# Energy-Meter.net
KiCad netlist of a schematic drawn in Altium Designer
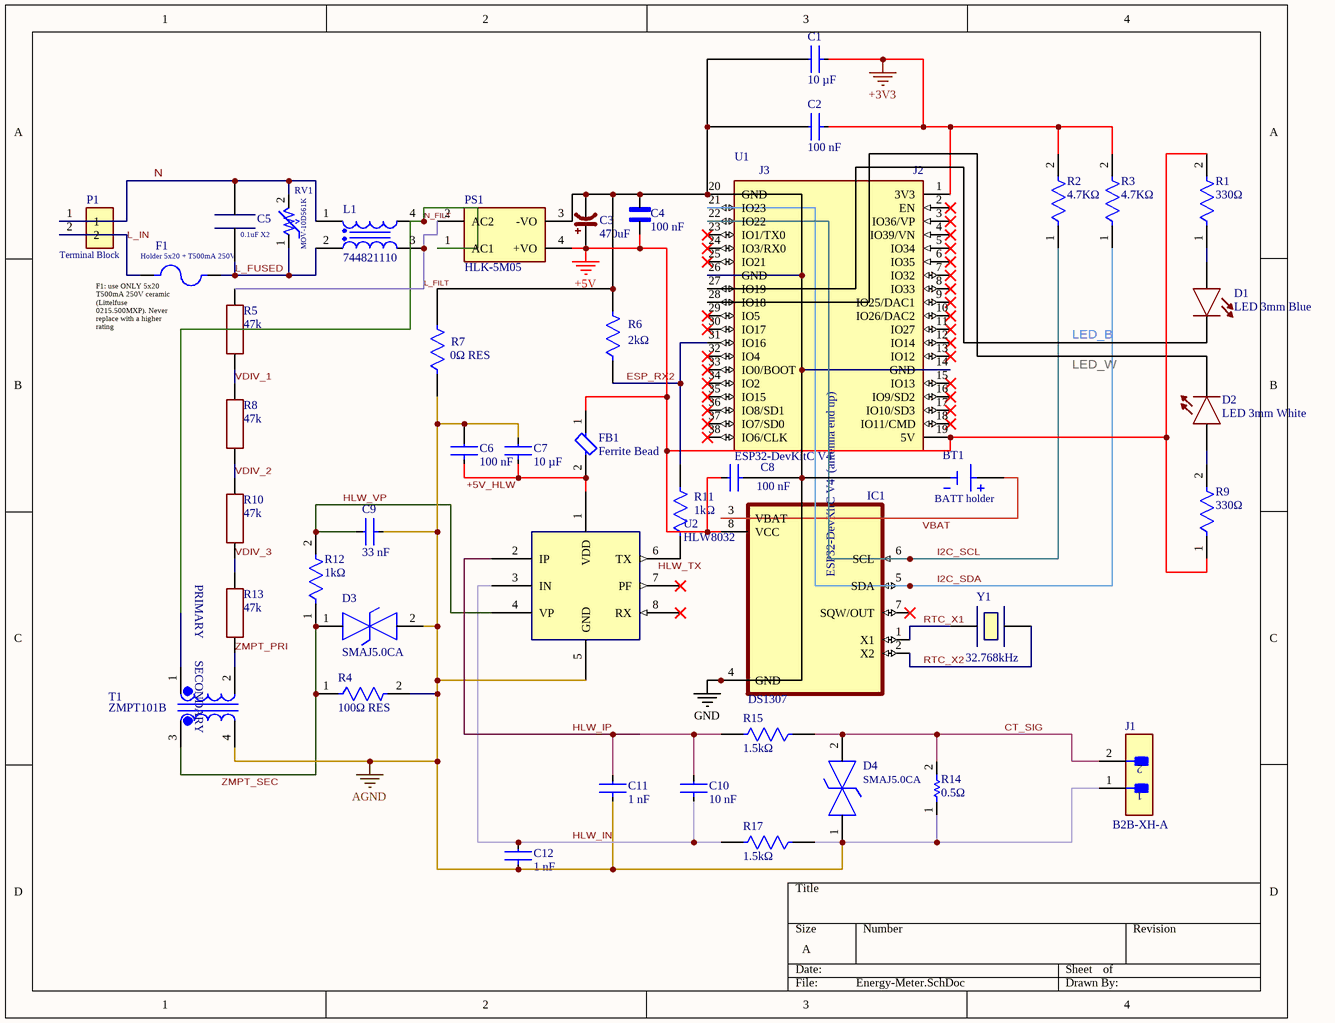
[diagram p0: Energy-Meter.SchDoc]

(export (version "E")
  (design (tool "Eeschema 10.0.6"))
  (components
    (comp (ref "BT1")
      (value "BATT holder")
      (footprint "BAT_BH32T-C-G")
      (description "BATTERY HOLDER COIN 20MM PC PIN")
      (fields (field (name "MANUFACTURER") "MPD") (field (name "MANUFACTURER PART NUMBER") "BH32T-C-G"))
      (libsource (lib "BH32T-C-G") (part "BH32T-C-G"))
    )
    (comp (ref "C1")
      (value "10 µF")
      (footprint "FP-1206-L_3_2_0_2-W_1_6_0-MFG")
      (description "General Purpose Ceramic Capacitor, 1206, 10uF, 10%, X5R, 15%, 10V")
      (fields (field (name "TOLERANCE") "10%") (field (name "VOLTAGE") "10V"))
      (libsource (lib "Components - 24.09.26 - 14.46") (part "CMP-04427-021870-1"))
    )
    (comp (ref "C2")
      (value "100 nF")
      (footprint "FP-C1206C-EB-MFG")
      (description "CAP CER 0.1UF 25V X7R 1206")
      (fields
        (field (name "OCTOPART") "https://octopart.com/c1206c104j3ractu-kemet-9140182")
        (field (name "MANUFACTURER") "KEMET")
      )
      (libsource (lib "Components - 24.09.26 - 14.39") (part "CMP-03020-014296-1"))
    )
    (comp (ref "C3")
      (value "470uF")
      (footprint "CAPPRD350W60D800H1150_LAYDOWN")
      (description "Capacitor, aluminium electrolytic, 470 uF, 10 V, 20%, radial D8x11.5mm, 3.5mm pitch, laid down")
      (fields (field (name "TOLERANCE") "±20%") (field (name "MANUFACTURER") "Rubycon"))
      (libsource (lib "Capacitor_470uF_10V_LayDown") (part "CAP_POL_470UF_10V_D8X11.5_LD"))
    )
    (comp (ref "C4")
      (value "100 nF")
      (footprint "CAPRR508W50L508T318H762")
      (description "AR 100nF Ceramic Multilayer Cap,50V dc,+125C,X7R Dielectric,+/-10%,Through Hole ¦ AVX AR215C104K4R")
      (fields (field (name "MANUFACTURER") "AVX") (field (name "MANUFACTURER PART NUMBER") "AR215C104K4R"))
      (libsource (lib "AR215C104K4R") (part "AR215C104K4R"))
    )
    (comp (ref "C5")
      (value "0.1uF X2")
      (footprint "CAPX2_L18.0-W6.0-H11.0_P15.00")
      (fields
        (field (name "MANUFACTURER") "TDK")
        (field (name "MANUFACTURER PART NUMBER") "B32922C3104K000")
        (field (name "TOLERANCE") "+/-10% (K)")
      )
      (libsource (lib "0.1uf-x2-capacitor") (part "CAP-X2-0.1uF-275VAC"))
    )
    (comp (ref "C6")
      (value "100 nF")
      (footprint "FP-C1206C-EB-MFG")
      (description "CAP CER 0.1UF 25V X7R 1206")
      (fields
        (field (name "OCTOPART") "https://octopart.com/c1206c104j3ractu-kemet-9140182")
        (field (name "MANUFACTURER") "KEMET")
      )
      (libsource (lib "Components - 24.09.26 - 14.39") (part "CMP-03020-014296-1"))
    )
    (comp (ref "C7")
      (value "10 µF")
      (footprint "FP-GRM31C-0_2-e0_3_0_8-IPC_C")
      (description "Chip Multilayer Ceramic Capacitors for General Purpose, 1206, 10uF, X7R, 15%, 10%, 25V")
      (fields (field (name "TOLERANCE") "10%") (field (name "VOLTAGE") "25V"))
      (libsource (lib "Components - 04.10.26 - 11.53") (part "CMP-06035-005515-1"))
    )
    (comp (ref "C8")
      (value "100 nF")
      (footprint "FP-C1206C-EB-MFG")
      (description "CAP CER 0.1UF 25V X7R 1206")
      (fields
        (field (name "OCTOPART") "https://octopart.com/c1206c104j3ractu-kemet-9140182")
        (field (name "MANUFACTURER") "KEMET")
      )
      (libsource (lib "Components - 24.09.26 - 14.39") (part "CMP-03020-014296-1"))
    )
    (comp (ref "C9")
      (value "33 nF")
      (footprint "FP-C1206C-EB-MFG")
      (description "C1206 33,000 pF C0G 5.00% 50 V")
      (fields
        (field (name "MANUFACTURER") "KEMET")
        (field (name "MANUFACTURER PART NUMBER") "C1206C333J5GACAUTO")
      )
      (libsource (lib "Components - 05.10.26 - 13.04") (part "CMP-03020-013243-1"))
    )
    (comp (ref "C10")
      (value "10 nF")
      (footprint "FP-C1206C-EB-MFG")
      (description "CAP CER 10000PF 100V C0G 1206")
      (fields
        (field (name "OCTOPART") "https://octopart.com/c1206c103j1gacauto-kemet-84841126")
        (field (name "TOLERANCE") "0.05")
      )
      (libsource (lib "Components - 05.10.26 - 11.35") (part "CMP-03020-012568-1"))
    )
    (comp (ref "C11")
      (value "1 nF")
      (footprint "FP-C1206C-EB-MFG")
      (description "C1206 1,000 pF C0G 5.00% 200 V")
      (fields
        (field (name "MANUFACTURER PART NUMBER") "C1206C102J2GACAUTO")
        (field (name "MANUFACTURER") "KEMET")
      )
      (libsource (lib "Components - 05.10.26 - 10.58") (part "CMP-03020-025981-1"))
    )
    (comp (ref "C12")
      (value "1 nF")
      (footprint "FP-C1206C-EB-MFG")
      (description "C1206 1,000 pF C0G 5.00% 200 V")
      (fields
        (field (name "MANUFACTURER PART NUMBER") "C1206C102J2GACAUTO")
        (field (name "MANUFACTURER") "KEMET")
      )
      (libsource (lib "Components - 05.10.26 - 10.58") (part "CMP-03020-025981-1"))
    )
    (comp (ref "D1")
      (value "LED 3mm Blue")
      (footprint "LED_D3.0MM_P2.54_BLUE")
      (description "LED, 3mm round, blue diffused, THT 2.54mm")
      (fields
        (field (name "MANUFACTURER") "Kingbright")
        (field (name "MANUFACTURER PART NUMBER") "WP710A10QBD/D")
      )
      (libsource (lib "LED_3mm_Blue_Diffused") (part "LED_3MM_BLUE_DIFFUSED"))
    )
    (comp (ref "D2")
      (value "LED 3mm White")
      (footprint "LED_D3.0MM_P2.54_WHITE")
      (description "LED, 3mm round, white diffused, THT 2.54mm")
      (fields
        (field (name "MANUFACTURER") "Kingbright")
        (field (name "MANUFACTURER PART NUMBER") "L-7104QWC-D")
      )
      (libsource (lib "LED_3mm_White_Diffused") (part "LED_3MM_WHITE_DIFFUSED"))
    )
    (comp (ref "D3")
      (value "SMAJ5.0CA")
      (footprint "FP-SMAJ-MFG")
      (description "TVS DIODE 5V 9.2V SMA")
      (fields
        (field (name "MANUFACTURER") "Bourns Inc.")
        (field (name "OCTOPART") "https://octopart.com/smaj5.0ca-bourns-12809390")
      )
      (libsource (lib "Components - 24.09.26 - 15.01") (part "CMP-2000-07091-2"))
    )
    (comp (ref "D4")
      (value "SMAJ5.0CA")
      (footprint "FP-SMAJ-MFG")
      (description "TVS DIODE 5V 9.2V SMA")
      (fields
        (field (name "MANUFACTURER") "Bourns Inc.")
        (field (name "OCTOPART") "https://octopart.com/smaj5.0ca-bourns-12809390")
      )
      (libsource (lib "Components - 24.09.26 - 15.01") (part "CMP-2000-07091-2"))
    )
    (comp (ref "F1")
      (value "Holder 5x20 + T500mA 250V")
      (footprint "FUSE_4628")
      (description "5mm Slim Line Fuse holder")
      (fields (field (name "MANUFACTURER") "Keystone") (field (name "MANUFACTURER PART NUMBER") "4628"))
      (libsource (lib "4628") (part "4628"))
    )
    (comp (ref "FB1")
      (value "Ferrite Bead")
      (footprint "FP-BLM31-0_2-t1_6-IPC_B")
      (description "Chip Ferrite Bead, 1206, 600Ω @ 100MHz, 0.038Ω, 25%, 2.9A")
      (fields (field (name "MANUFACTURER") "125°C"))
      (libsource (lib "Components - 20.09.26 - 18.12") (part "CMP-06046-002432-1"))
    )
    (comp (ref "IC1")
      (value "DS1307")
      (footprint "DIP794W47P254L991H457Q8")
      (description "Real Time Clock (RTC) I²C, 56 B RAM, 8-DIP")
      (fields
        (field (name "MANUFACTURER") "Analog Devices")
        (field (name "MANUFACTURER PART NUMBER") "DS1307+")
      )
      (libsource (lib "DS1307") (part "DS1307"))
    )
    (comp (ref "J1")
      (value "B2B-XH-A")
      (footprint "FP-B2B-XH-AM_LF_SN-MFG")
      (description "CONN HEADER VERT 2POS 2.5MM")
      (fields
        (field (name "MANUFACTURER") "JST")
        (field (name "MANUFACTURER PART NUMBER") "B2B-XH-AM(LF)(SN)")
      )
      (libsource (lib "Components - 27.09.26 - 13.44") (part "CMP-17439-000037-1"))
    )
    (comp (ref "L1")
      (value "744821110")
      (footprint "WE-CMB_Type XS_L15W7.5H18")
      (fields (field (name "TOLERANCE") "30%") (field (name "MANUFACTURER") "Wurth Elektronik"))
      (libsource (lib "Components - 02.10.26 - 18.05") (part "CMP-0223-00077-2"))
    )
    (comp (ref "P1")
      (value "Terminal Block")
      (footprint "TE_282837-2")
      (fields
        (field (name "MANUFACTURER") "TE Connectivity")
        (field (name "MANUFACTURER PART NUMBER") "282837-2")
      )
      (libsource (lib "282837-2") (part "282837-2"))
    )
    (comp (ref "PS1")
      (value "HLK-5M05")
      (footprint "CONV_HLK-5M05")
      (description "AC DC 220V to 5V 5W 5Watt Isolated Switching Step-Down Power Supply Module Converter")
      (fields (field (name "MANUFACTURER") "Hi-link"))
      (libsource (lib "Smart-Energy-Meter") (part "HLK-5M05"))
    )
    (comp (ref "R1")
      (value "330Ω")
      (footprint "FP-AC2512-MFG")
      (description "RES SMD 330 OHM 5% 1W 2512")
      (fields (field (name "MANUFACTURER") "Yageo") (field (name "TOLERANCE") "0.05"))
      (libsource (lib "Components - 27.09.26 - 08.47") (part "CMP-03412-030391-1"))
    )
    (comp (ref "R2")
      (value "4.7KΩ")
      (footprint "FP-AC2512-MFG")
      (description "RES SMD 4.7K OHM 1% 1W 2512")
      (fields
        (field (name "MANUFACTURER") "Yageo")
        (field (name "OCTOPART") "https://octopart.com/ac2512fk-074k7l-yageo-71370127")
      )
      (libsource (lib "Components - 26.09.26 - 14.01") (part "CMP-03412-032212-1"))
    )
    (comp (ref "R3")
      (value "4.7KΩ")
      (footprint "FP-AC2512-MFG")
      (description "RES SMD 4.7K OHM 1% 1W 2512")
      (fields
        (field (name "MANUFACTURER") "Yageo")
        (field (name "OCTOPART") "https://octopart.com/ac2512fk-074k7l-yageo-71370127")
      )
      (libsource (lib "Components - 26.09.26 - 14.01") (part "CMP-03412-032212-1"))
    )
    (comp (ref "R4")
      (value "100Ω RES")
      (footprint "FP-MCA1206-IPC_A")
      (description "Res MC AT Precision Thin Film 1206 100Ω 0.1% 0.4W ±25ppm/°C Molded Paper T/R")
      (fields (field (name "TOLERANCE") "0.1%") (field (name "MANUFACTURER") "Vishay"))
      (libsource (lib "Components - 04.10.26 - 07.59") (part "CMP-02407-001396-1"))
    )
    (comp (ref "R5")
      (value "47k")
      (footprint "RESAD762W55L630D240_MF")
      (description "Resistor, 47 kOhm, 1%, 0.25 W, metal film, axial THT, 7.62 mm pitch")
      (fields (field (name "TOLERANCE") "±1%") (field (name "POWER") "0.25W (1/4W)"))
      (libsource (lib "Resistor_47K_1pct_MetalFilm_THT") (part "RES_47K_0.25W_1PCT_MF_7.62MM"))
    )
    (comp (ref "R6")
      (value "2kΩ")
      (footprint "FP-CRCW2512-e3-IPC_A")
      (description "RES Thick Film, 2kΩ, 1%, 1W, 100ppm/°C, 2512")
      (fields (field (name "TOLERANCE") "1%") (field (name "MANUFACTURER") "Vishay"))
      (libsource (lib "Components - 27.09.26 - 07.57") (part "CMP-02407-009223-1"))
    )
    (comp (ref "R7")
      (value "0Ω RES")
      (footprint "FP-RMCF2512-IPC_A")
      (description "0Ω ±0 1W 2512 Thick Film Chip Resistor AEC-Q200 compliant")
      (fields (field (name "TOLERANCE") "5%") (field (name "MANUFACTURER") "Stackpole"))
      (libsource (lib "Components - 27.09.26 - 08.03") (part "CMP-26527-000191-1"))
    )
    (comp (ref "R8")
      (value "47k")
      (footprint "RESAD762W55L630D240_MF")
      (description "Resistor, 47 kOhm, 1%, 0.25 W, metal film, axial THT, 7.62 mm pitch")
      (fields (field (name "TOLERANCE") "±1%") (field (name "POWER") "0.25W (1/4W)"))
      (libsource (lib "Resistor_47K_1pct_MetalFilm_THT") (part "RES_47K_0.25W_1PCT_MF_7.62MM"))
    )
    (comp (ref "R9")
      (value "330Ω")
      (footprint "FP-AC2512-MFG")
      (description "RES SMD 330 OHM 5% 1W 2512")
      (fields (field (name "MANUFACTURER") "Yageo") (field (name "TOLERANCE") "0.05"))
      (libsource (lib "Components - 27.09.26 - 08.47") (part "CMP-03412-030391-1"))
    )
    (comp (ref "R10")
      (value "47k")
      (footprint "RESAD762W55L630D240_MF")
      (description "Resistor, 47 kOhm, 1%, 0.25 W, metal film, axial THT, 7.62 mm pitch")
      (fields (field (name "TOLERANCE") "±1%") (field (name "POWER") "0.25W (1/4W)"))
      (libsource (lib "Resistor_47K_1pct_MetalFilm_THT") (part "RES_47K_0.25W_1PCT_MF_7.62MM"))
    )
    (comp (ref "R11")
      (value "1kΩ")
      (footprint "FP-CRCW2512-e3-IPC_A")
      (description "RES Thick Film, 1kΩ, 1%, 1W, 100ppm/°C, 2512")
      (fields (field (name "TOLERANCE") "1%") (field (name "MANUFACTURER") "Vishay"))
      (libsource (lib "Components - 26.09.26 - 13.02") (part "CMP-02407-005908-1"))
    )
    (comp (ref "R12")
      (value "1kΩ")
      (footprint "FP-RMCF1206-IPC_C")
      (description "1kΩ ±1% 0.25W 1206 Thick Film Chip Resistor AEC-Q200 compliant")
      (fields (field (name "TOLERANCE") "1%") (field (name "MANUFACTURER") "155°C"))
      (libsource (lib "Components - 24.09.26 - 14.09") (part "CMP-26527-005571-1"))
    )
    (comp (ref "R13")
      (value "47k")
      (footprint "RESAD762W55L630D240_MF")
      (description "Resistor, 47 kOhm, 1%, 0.25 W, metal film, axial THT, 7.62 mm pitch")
      (fields (field (name "TOLERANCE") "±1%") (field (name "POWER") "0.25W (1/4W)"))
      (libsource (lib "Resistor_47K_1pct_MetalFilm_THT") (part "RES_47K_0.25W_1PCT_MF_7.62MM"))
    )
    (comp (ref "R14")
      (value "0.5Ω")
      (footprint "RESC6432X89X76ML25T25")
      (description "Chip Resistor, 0.5 Ohm, +/- 1%, 1 W, -65 to 275 degC, 2512 (6432 Metric), RoHS, Tape and Reel")
      (fields (field (name "TOLERANCE") "1%") (field (name "MANUFACTURER PART NUMBER") "WSLT2512R5000FEA"))
      (libsource (lib "Components - 04.10.26 - 11.37") (part "CMP-1666-00017-2"))
    )
    (comp (ref "R15")
      (value "1.5kΩ")
      (footprint "FP-CRCW2512-e3-IPC_A")
      (description "RES Thick Film, 1.5kΩ, 1%, 1W, 100ppm/°C, 2512")
      (fields (field (name "TOLERANCE") "1%") (field (name "MANUFACTURER") "Vishay"))
      (libsource (lib "Components - 26.09.26 - 13.06") (part "CMP-02407-008685-1"))
    )
    (comp (ref "R17")
      (value "1.5kΩ")
      (footprint "FP-CRCW2512-e3-IPC_A")
      (description "RES Thick Film, 1.5kΩ, 1%, 1W, 100ppm/°C, 2512")
      (fields (field (name "TOLERANCE") "1%") (field (name "MANUFACTURER") "Vishay"))
      (libsource (lib "Components - 26.09.26 - 13.06") (part "CMP-02407-008685-1"))
    )
    (comp (ref "RV1")
      (value "MOV-10D561K")
      (footprint "VAR_MOV-10D561K")
      (description "560 V 2.5 kA Varistor 1 Circuit Through Hole Disc 10mm")
      (fields (field (name "MANUFACTURER") "Bourns"))
      (libsource (lib "MOV-10D561K") (part "MOV-10D561K"))
    )
    (comp (ref "T1")
      (value "ZMPT101B")
      (footprint "XFMR_ZMPT101B")
      (description "Current-type Voltage Transformer")
      (fields (field (name "MANUFACTURER") "Qingxian Zeming Langxi Electronic"))
      (libsource (lib "ZMPT101B") (part "ZMPT101B"))
    )
    (comp (ref "U1")
      (value "ESP32-DevKitC V4")
      (footprint "ESP32-DEVKITC-V4_SOCKET")
      (description "Espressif ESP32-DevKitC V4 (ESP32-WROOM-32E) dev board, socketed on 2x19 female headers")
      (fields
        (field (name "MANUFACTURER") "Espressif Systems")
        (field (name "MANUFACTURER PART NUMBER") "ESP32-DEVKITC-32E")
      )
      (libsource (lib "ESP32_DevKitC_V4_Socket") (part "ESP32-DEVKITC-V4"))
    )
    (comp (ref "U2")
      (value "HLW8032")
      (footprint "SOIC127P600X175-8N")
      (fields (field (name "MANUFACTURER") "Hiliwei Tech"))
      (libsource (lib "Smart-Energy-Meter") (part "HLW8032"))
    )
    (comp (ref "Y1")
      (value "32.768kHz")
      (footprint "XTAL_D3.2xL8.3_P2.00_Vertical")
      (fields
        (field (name "TOLERANCE") "+/-20ppm")
        (field (name "MANUFACTURER PART NUMBER") "AB38T-32.768KHZ")
        (field (name "MANUFACTURER") "Abracon")
      )
      (libsource (lib "Crystal_32768") (part "XTAL-32.768kHz"))
    )
  )
  (nets
    (net (code "1") (name "+3V3") (class "Default")
      (node (ref "C1") (pin "1") (pinfunction "1_1") (pintype "passive"))
      (node (ref "C2") (pin "1") (pinfunction "1_1") (pintype "passive"))
      (node (ref "R2") (pin "2") (pinfunction "2_2") (pintype "passive"))
      (node (ref "R3") (pin "2") (pinfunction "2_2") (pintype "passive"))
      (node (ref "U1") (pin "1") (pinfunction "3V3_1") (pintype "power_in"))
    )
    (net (code "2") (name "+5V") (class "Default")
      (node (ref "C3") (pin "1") (pinfunction "+_1") (pintype "passive"))
      (node (ref "C4") (pin "1") (pinfunction "1_1") (pintype "passive"))
      (node (ref "C8") (pin "2") (pinfunction "2_2") (pintype "passive"))
      (node (ref "FB1") (pin "1") (pinfunction "1_1") (pintype "passive"))
      (node (ref "IC1") (pin "8") (pinfunction "VCC_8") (pintype "power_in"))
      (node (ref "PS1") (pin "4") (pinfunction "+VO_4") (pintype "power_in"))
      (node (ref "R1") (pin "2") (pinfunction "2_2") (pintype "passive"))
      (node (ref "R9") (pin "1") (pinfunction "1_1") (pintype "passive"))
      (node (ref "U1") (pin "19") (pinfunction "5V_19") (pintype "power_in"))
    )
    (net (code "3") (name "/+5V_HLW") (class "Default")
      (node (ref "C6") (pin "1") (pinfunction "1_1") (pintype "passive"))
      (node (ref "C7") (pin "1") (pinfunction "1_1") (pintype "passive"))
      (node (ref "FB1") (pin "2") (pinfunction "2_2") (pintype "passive"))
      (node (ref "U2") (pin "1") (pinfunction "VDD_1") (pintype "power_in"))
    )
    (net (code "4") (name "/CT_SIG") (class "Default")
      (node (ref "D4") (pin "2") (pinfunction "2_2") (pintype "passive"))
      (node (ref "J1") (pin "2") (pinfunction "2_2") (pintype "passive"))
      (node (ref "R14") (pin "2") (pinfunction "2_2") (pintype "passive"))
      (node (ref "R15") (pin "1") (pinfunction "1_1") (pintype "passive"))
    )
    (net (code "5") (name "/ESP_RX2") (class "Default")
      (node (ref "R11") (pin "2") (pinfunction "2_2") (pintype "passive"))
      (node (ref "R6") (pin "1") (pinfunction "1_1") (pintype "passive"))
      (node (ref "U1") (pin "31") (pinfunction "IO16_31") (pintype "bidirectional"))
    )
    (net (code "6") (name "/HLW_IN") (class "Default")
      (node (ref "C10") (pin "1") (pinfunction "1_1") (pintype "passive"))
      (node (ref "C12") (pin "2") (pinfunction "2_2") (pintype "passive"))
      (node (ref "R17") (pin "2") (pinfunction "2_2") (pintype "passive"))
      (node (ref "U2") (pin "3") (pinfunction "IN_3") (pintype "passive"))
    )
    (net (code "7") (name "/HLW_IP") (class "Default")
      (node (ref "C10") (pin "2") (pinfunction "2_2") (pintype "passive"))
      (node (ref "C11") (pin "2") (pinfunction "2_2") (pintype "passive"))
      (node (ref "R15") (pin "2") (pinfunction "2_2") (pintype "passive"))
      (node (ref "U2") (pin "2") (pinfunction "IP_2") (pintype "passive"))
    )
    (net (code "8") (name "/HLW_TX") (class "Default")
      (node (ref "R11") (pin "1") (pinfunction "1_1") (pintype "passive"))
      (node (ref "U2") (pin "6") (pinfunction "TX_6") (pintype "output"))
    )
    (net (code "9") (name "/HLW_VP") (class "Default")
      (node (ref "C9") (pin "2") (pinfunction "2_2") (pintype "passive"))
      (node (ref "R12") (pin "2") (pinfunction "2_2") (pintype "passive"))
      (node (ref "U2") (pin "4") (pinfunction "VP_4") (pintype "passive"))
    )
    (net (code "10") (name "/I2C_SCL") (class "Default")
      (node (ref "IC1") (pin "6") (pinfunction "SCL_6") (pintype "input"))
      (node (ref "R2") (pin "1") (pinfunction "1_1") (pintype "passive"))
      (node (ref "U1") (pin "22") (pinfunction "IO22_22") (pintype "bidirectional"))
    )
    (net (code "11") (name "/I2C_SDA") (class "Default")
      (node (ref "IC1") (pin "5") (pinfunction "SDA_5") (pintype "bidirectional"))
      (node (ref "R3") (pin "1") (pinfunction "1_1") (pintype "passive"))
      (node (ref "U1") (pin "21") (pinfunction "IO23_21") (pintype "bidirectional"))
    )
    (net (code "12") (name "/LED_B") (class "Default")
      (node (ref "D1") (pin "1") (pinfunction "K_1") (pintype "passive"))
      (node (ref "U1") (pin "27") (pinfunction "IO19_27") (pintype "bidirectional"))
    )
    (net (code "13") (name "/LED_W") (class "Default")
      (node (ref "D2") (pin "1") (pinfunction "K_1") (pintype "passive"))
      (node (ref "U1") (pin "28") (pinfunction "IO18_28") (pintype "bidirectional"))
    )
    (net (code "14") (name "/L_FILT") (class "Default")
      (node (ref "L1") (pin "3") (pinfunction "3_3") (pintype "passive"))
      (node (ref "PS1") (pin "2") (pinfunction "AC2_2") (pintype "passive"))
      (node (ref "R5") (pin "2") (pinfunction "2_2") (pintype "passive"))
    )
    (net (code "15") (name "/L_FUSED") (class "Default")
      (node (ref "C5") (pin "1") (pinfunction "1_1") (pintype "passive"))
      (node (ref "F1") (pin "2") (pinfunction "2_2") (pintype "passive"))
      (node (ref "L1") (pin "2") (pinfunction "2_2") (pintype "passive"))
      (node (ref "RV1") (pin "1") (pinfunction "1_1") (pintype "passive"))
    )
    (net (code "16") (name "/L_IN") (class "Default")
      (node (ref "F1") (pin "1") (pinfunction "1_1") (pintype "passive"))
      (node (ref "P1") (pin "2") (pinfunction "2_2") (pintype "passive"))
    )
    (net (code "17") (name "/N") (class "Default")
      (node (ref "C5") (pin "2") (pinfunction "2_2") (pintype "passive"))
      (node (ref "L1") (pin "1") (pinfunction "1_1") (pintype "passive"))
      (node (ref "P1") (pin "1") (pinfunction "1_1") (pintype "passive"))
      (node (ref "RV1") (pin "2") (pinfunction "2_2") (pintype "passive"))
    )
    (net (code "18") (name "/N_FILT") (class "Default")
      (node (ref "L1") (pin "4") (pinfunction "4_4") (pintype "passive"))
      (node (ref "PS1") (pin "1") (pinfunction "AC1_1") (pintype "passive"))
      (node (ref "T1") (pin "1") (pinfunction "1_1") (pintype "passive"))
    )
    (net (code "19") (name "/RTC_X1") (class "Default")
      (node (ref "IC1") (pin "1") (pinfunction "X1_1") (pintype "bidirectional"))
      (node (ref "Y1") (pin "1") (pinfunction "1_1") (pintype "passive"))
    )
    (net (code "20") (name "/RTC_X2") (class "Default")
      (node (ref "IC1") (pin "2") (pinfunction "X2_2") (pintype "bidirectional"))
      (node (ref "Y1") (pin "2") (pinfunction "2_2") (pintype "passive"))
    )
    (net (code "21") (name "/VBAT") (class "Default")
      (node (ref "BT1") (pin "POS") (pinfunction "POS_POS") (pintype "passive"))
      (node (ref "IC1") (pin "3") (pinfunction "VBAT_3") (pintype "power_in"))
    )
    (net (code "22") (name "/VDIV_1") (class "Default")
      (node (ref "R5") (pin "1") (pinfunction "1_1") (pintype "passive"))
      (node (ref "R8") (pin "2") (pinfunction "2_2") (pintype "passive"))
    )
    (net (code "23") (name "/VDIV_2") (class "Default")
      (node (ref "R10") (pin "2") (pinfunction "2_2") (pintype "passive"))
      (node (ref "R8") (pin "1") (pinfunction "1_1") (pintype "passive"))
    )
    (net (code "24") (name "/VDIV_3") (class "Default")
      (node (ref "R10") (pin "1") (pinfunction "1_1") (pintype "passive"))
      (node (ref "R13") (pin "2") (pinfunction "2_2") (pintype "passive"))
    )
    (net (code "25") (name "/ZMPT_PRI") (class "Default")
      (node (ref "R13") (pin "1") (pinfunction "1_1") (pintype "passive"))
      (node (ref "T1") (pin "2") (pinfunction "2_2") (pintype "passive"))
    )
    (net (code "26") (name "/ZMPT_SEC") (class "Default")
      (node (ref "D3") (pin "1") (pinfunction "1_1") (pintype "passive"))
      (node (ref "R12") (pin "1") (pinfunction "1_1") (pintype "passive"))
      (node (ref "R4") (pin "1") (pinfunction "1_1") (pintype "passive"))
      (node (ref "T1") (pin "3") (pinfunction "3_3") (pintype "passive"))
    )
    (net (code "27") (name "AGND") (class "Default")
      (node (ref "C11") (pin "1") (pinfunction "1_1") (pintype "passive"))
      (node (ref "C12") (pin "1") (pinfunction "1_1") (pintype "passive"))
      (node (ref "C6") (pin "2") (pinfunction "2_2") (pintype "passive"))
      (node (ref "C7") (pin "2") (pinfunction "2_2") (pintype "passive"))
      (node (ref "C9") (pin "1") (pinfunction "1_1") (pintype "passive"))
      (node (ref "D3") (pin "2") (pinfunction "2_2") (pintype "passive"))
      (node (ref "D4") (pin "1") (pinfunction "1_1") (pintype "passive"))
      (node (ref "J1") (pin "1") (pinfunction "1_1") (pintype "passive"))
      (node (ref "R14") (pin "1") (pinfunction "1_1") (pintype "passive"))
      (node (ref "R17") (pin "1") (pinfunction "1_1") (pintype "passive"))
      (node (ref "R4") (pin "2") (pinfunction "2_2") (pintype "passive"))
      (node (ref "R7") (pin "1") (pinfunction "1_1") (pintype "passive"))
      (node (ref "T1") (pin "4") (pinfunction "4_4") (pintype "passive"))
      (node (ref "U2") (pin "5") (pinfunction "GND_5") (pintype "power_in"))
    )
    (net (code "28") (name "GND") (class "Default")
      (node (ref "BT1") (pin "NEG") (pinfunction "NEG_NEG") (pintype "passive"))
      (node (ref "C1") (pin "2") (pinfunction "2_2") (pintype "passive"))
      (node (ref "C2") (pin "2") (pinfunction "2_2") (pintype "passive"))
      (node (ref "C3") (pin "2") (pinfunction "-_2") (pintype "passive"))
      (node (ref "C4") (pin "2") (pinfunction "2_2") (pintype "passive"))
      (node (ref "C8") (pin "1") (pinfunction "1_1") (pintype "passive"))
      (node (ref "IC1") (pin "4") (pinfunction "GND_4") (pintype "power_in"))
      (node (ref "PS1") (pin "3") (pinfunction "-VO_3") (pintype "power_in"))
      (node (ref "R6") (pin "2") (pinfunction "2_2") (pintype "passive"))
      (node (ref "R7") (pin "2") (pinfunction "2_2") (pintype "passive"))
      (node (ref "U1") (pin "14") (pinfunction "GND_14") (pintype "power_in"))
      (node (ref "U1") (pin "20") (pinfunction "GND_20") (pintype "power_in"))
      (node (ref "U1") (pin "26") (pinfunction "GND_26") (pintype "power_in"))
    )
    (net (code "29") (name "Net-(D1-A)") (class "Default")
      (node (ref "D1") (pin "2") (pinfunction "A_2") (pintype "passive"))
      (node (ref "R1") (pin "1") (pinfunction "1_1") (pintype "passive"))
    )
    (net (code "30") (name "Net-(D2-A)") (class "Default")
      (node (ref "D2") (pin "2") (pinfunction "A_2") (pintype "passive"))
      (node (ref "R9") (pin "2") (pinfunction "2_2") (pintype "passive"))
    )
    (net (code "31") (name "unconnected-(IC1-SQW{slash}OUT-Pad7)") (class "Default")
      (node (ref "IC1") (pin "7") (pinfunction "SQW/OUT_7") (pintype "bidirectional+no_connect"))
    )
    (net (code "32") (name "unconnected-(U1-EN-Pad2)") (class "Default")
      (node (ref "U1") (pin "2") (pinfunction "EN_2") (pintype "input+no_connect"))
    )
    (net (code "33") (name "unconnected-(U1-IO0{slash}BOOT-Pad33)") (class "Default")
      (node (ref "U1") (pin "33") (pinfunction "IO0/BOOT_33") (pintype "bidirectional+no_connect"))
    )
    (net (code "34") (name "unconnected-(U1-IO1{slash}TX0-Pad23)") (class "Default")
      (node (ref "U1") (pin "23") (pinfunction "IO1/TX0_23") (pintype "bidirectional+no_connect"))
    )
    (net (code "35") (name "unconnected-(U1-IO2-Pad34)") (class "Default")
      (node (ref "U1") (pin "34") (pinfunction "IO2_34") (pintype "bidirectional+no_connect"))
    )
    (net (code "36") (name "unconnected-(U1-IO3{slash}RX0-Pad24)") (class "Default")
      (node (ref "U1") (pin "24") (pinfunction "IO3/RX0_24") (pintype "bidirectional+no_connect"))
    )
    (net (code "37") (name "unconnected-(U1-IO4-Pad32)") (class "Default")
      (node (ref "U1") (pin "32") (pinfunction "IO4_32") (pintype "bidirectional+no_connect"))
    )
    (net (code "38") (name "unconnected-(U1-IO5-Pad29)") (class "Default")
      (node (ref "U1") (pin "29") (pinfunction "IO5_29") (pintype "bidirectional+no_connect"))
    )
    (net (code "39") (name "unconnected-(U1-IO6{slash}CLK-Pad38)") (class "Default")
      (node (ref "U1") (pin "38") (pinfunction "IO6/CLK_38") (pintype "bidirectional+no_connect"))
    )
    (net (code "40") (name "unconnected-(U1-IO7{slash}SD0-Pad37)") (class "Default")
      (node (ref "U1") (pin "37") (pinfunction "IO7/SD0_37") (pintype "bidirectional+no_connect"))
    )
    (net (code "41") (name "unconnected-(U1-IO8{slash}SD1-Pad36)") (class "Default")
      (node (ref "U1") (pin "36") (pinfunction "IO8/SD1_36") (pintype "bidirectional+no_connect"))
    )
    (net (code "42") (name "unconnected-(U1-IO9{slash}SD2-Pad16)") (class "Default")
      (node (ref "U1") (pin "16") (pinfunction "IO9/SD2_16") (pintype "bidirectional+no_connect"))
    )
    (net (code "43") (name "unconnected-(U1-IO10{slash}SD3-Pad17)") (class "Default")
      (node (ref "U1") (pin "17") (pinfunction "IO10/SD3_17") (pintype "bidirectional+no_connect"))
    )
    (net (code "44") (name "unconnected-(U1-IO11{slash}CMD-Pad18)") (class "Default")
      (node (ref "U1") (pin "18") (pinfunction "IO11/CMD_18") (pintype "bidirectional+no_connect"))
    )
    (net (code "45") (name "unconnected-(U1-IO12-Pad13)") (class "Default")
      (node (ref "U1") (pin "13") (pinfunction "IO12_13") (pintype "bidirectional+no_connect"))
    )
    (net (code "46") (name "unconnected-(U1-IO13-Pad15)") (class "Default")
      (node (ref "U1") (pin "15") (pinfunction "IO13_15") (pintype "bidirectional+no_connect"))
    )
    (net (code "47") (name "unconnected-(U1-IO14-Pad12)") (class "Default")
      (node (ref "U1") (pin "12") (pinfunction "IO14_12") (pintype "bidirectional+no_connect"))
    )
    (net (code "48") (name "unconnected-(U1-IO15-Pad35)") (class "Default")
      (node (ref "U1") (pin "35") (pinfunction "IO15_35") (pintype "bidirectional+no_connect"))
    )
    (net (code "49") (name "unconnected-(U1-IO17-Pad30)") (class "Default")
      (node (ref "U1") (pin "30") (pinfunction "IO17_30") (pintype "bidirectional+no_connect"))
    )
    (net (code "50") (name "unconnected-(U1-IO21-Pad25)") (class "Default")
      (node (ref "U1") (pin "25") (pinfunction "IO21_25") (pintype "bidirectional+no_connect"))
    )
    (net (code "51") (name "unconnected-(U1-IO25{slash}DAC1-Pad9)") (class "Default")
      (node (ref "U1") (pin "9") (pinfunction "IO25/DAC1_9") (pintype "bidirectional+no_connect"))
    )
    (net (code "52") (name "unconnected-(U1-IO26{slash}DAC2-Pad10)") (class "Default")
      (node (ref "U1") (pin "10") (pinfunction "IO26/DAC2_10") (pintype "bidirectional+no_connect"))
    )
    (net (code "53") (name "unconnected-(U1-IO27-Pad11)") (class "Default")
      (node (ref "U1") (pin "11") (pinfunction "IO27_11") (pintype "bidirectional+no_connect"))
    )
    (net (code "54") (name "unconnected-(U1-IO32-Pad7)") (class "Default")
      (node (ref "U1") (pin "7") (pinfunction "IO32_7") (pintype "bidirectional+no_connect"))
    )
    (net (code "55") (name "unconnected-(U1-IO33-Pad8)") (class "Default")
      (node (ref "U1") (pin "8") (pinfunction "IO33_8") (pintype "bidirectional+no_connect"))
    )
    (net (code "56") (name "unconnected-(U1-IO34-Pad5)") (class "Default")
      (node (ref "U1") (pin "5") (pinfunction "IO34_5") (pintype "input+no_connect"))
    )
    (net (code "57") (name "unconnected-(U1-IO35-Pad6)") (class "Default")
      (node (ref "U1") (pin "6") (pinfunction "IO35_6") (pintype "input+no_connect"))
    )
    (net (code "58") (name "unconnected-(U1-IO36{slash}VP-Pad3)") (class "Default")
      (node (ref "U1") (pin "3") (pinfunction "IO36/VP_3") (pintype "input+no_connect"))
    )
    (net (code "59") (name "unconnected-(U1-IO39{slash}VN-Pad4)") (class "Default")
      (node (ref "U1") (pin "4") (pinfunction "IO39/VN_4") (pintype "input+no_connect"))
    )
    (net (code "60") (name "unconnected-(U2-PF-Pad7)") (class "Default")
      (node (ref "U2") (pin "7") (pinfunction "PF_7") (pintype "output+no_connect"))
    )
    (net (code "61") (name "unconnected-(U2-RX-Pad8)") (class "Default")
      (node (ref "U2") (pin "8") (pinfunction "RX_8") (pintype "input+no_connect"))
    )
  )
)
